# Power.net
KiCad netlist of a schematic drawn in Altium Designer
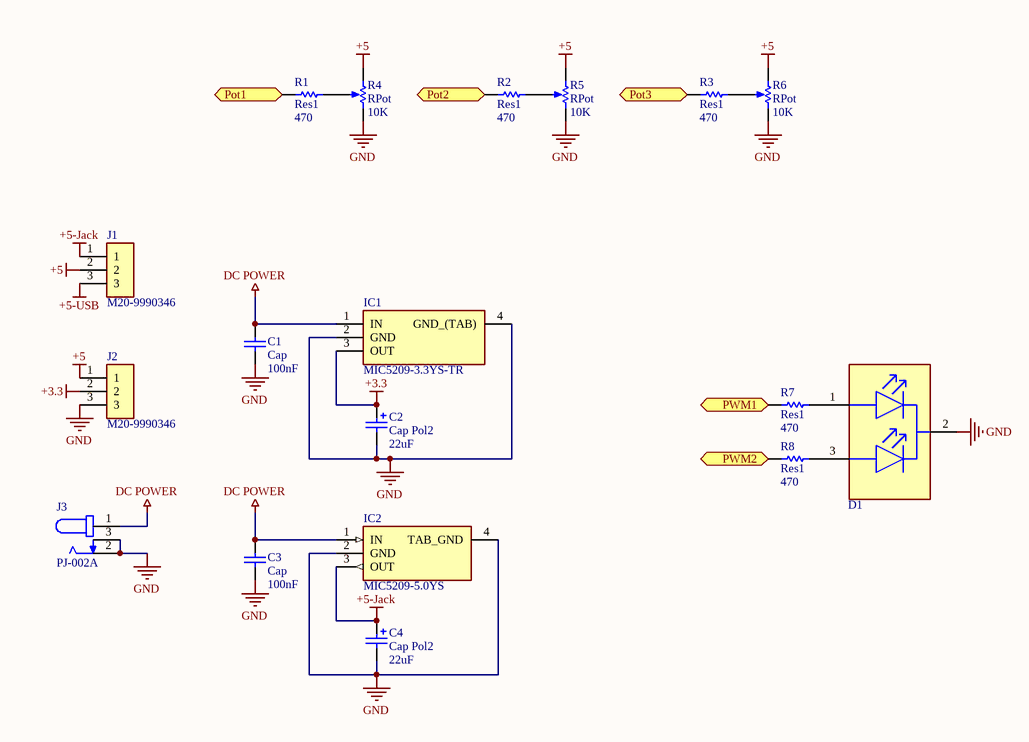
[diagram p0: Power.SchDoc]

(export (version "E")
  (design (tool "Eeschema 10.0.6"))
  (components
    (comp (ref "C1")
      (value "Cap")
      (footprint "Cap 100nF")
      (description "Capacitor")
      (fields (field (name "ALTIUM_VALUE") "100nF") (field (name "PUBLISHER") "Altium Limited"))
      (libsource (lib "APD") (part "Cap"))
    )
    (comp (ref "C2")
      (value "Cap Pol2")
      (footprint "CAP+ 22UF")
      (description "Polarized Capacitor (Axial)")
      (fields (field (name "ALTIUM_VALUE") "22uF") (field (name "PUBLISHER") "Altium Limited"))
      (libsource (lib "APD") (part "Cap Pol2"))
    )
    (comp (ref "C3")
      (value "Cap")
      (footprint "Cap 100nF")
      (description "Capacitor")
      (fields (field (name "ALTIUM_VALUE") "100nF") (field (name "PUBLISHER") "Altium Limited"))
      (libsource (lib "APD") (part "Cap"))
    )
    (comp (ref "C4")
      (value "Cap Pol2")
      (footprint "CAP+ 22UF")
      (description "Polarized Capacitor (Axial)")
      (fields (field (name "ALTIUM_VALUE") "22uF") (field (name "PUBLISHER") "Altium Limited"))
      (libsource (lib "APD") (part "Cap Pol2"))
    )
    (comp (ref "D1")
      (value "LTL1BEKVJNN")
      (footprint "Bicolor LED")
      (libsource (lib "APD") (part "LTL1BEKVJNN"))
    )
    (comp (ref "IC1")
      (value "MIC5209-3.3YS-TR")
      (footprint "LDO")
      (description "Integrated Circuit")
      (fields (field (name "MOUSER PART NUMBER") "998-MIC5209-3.3YSTR"))
      (libsource (lib "APD") (part "MIC5209-3.3YS-TR"))
    )
    (comp (ref "IC2")
      (value "MIC5209-5.0YS")
      (footprint "LDO")
      (description "Integrated Circuit")
      (fields (field (name "MOUSER PART NUMBER") "998-MIC5209-5.0YS"))
      (libsource (lib "APD") (part "MIC5209-5.0YS"))
    )
    (comp (ref "J1")
      (value "M20-9990346")
      (footprint "header 3 pins male")
      (description "Connector")
      (fields (field (name "MOUSER PART NUMBER") "855-M20-9990346"))
      (libsource (lib "APD") (part "M20-9990346"))
    )
    (comp (ref "J2")
      (value "M20-9990346")
      (footprint "Header 3 pins fem.")
      (description "Connector")
      (fields (field (name "MOUSER PART NUMBER") "855-M20-9990346"))
      (libsource (lib "APD") (part "M20-9990346"))
    )
    (comp (ref "J3")
      (value "PJ-002A")
      (footprint "DC Jack")
      (description "DC jack")
      (fields (field (name "MF") "CUI Devices"))
      (libsource (lib "APD") (part "PJ-002A"))
    )
    (comp (ref "R1")
      (value "Res1")
      (footprint "Resistor 1210")
      (description "Resistor")
      (fields (field (name "ALTIUM_VALUE") "470") (field (name "PUBLISHER") "Altium Limited"))
      (libsource (lib "APD") (part "Res1"))
    )
    (comp (ref "R2")
      (value "Res1")
      (footprint "Resistor 1210")
      (description "Resistor")
      (fields (field (name "ALTIUM_VALUE") "470") (field (name "PUBLISHER") "Altium Limited"))
      (libsource (lib "APD") (part "Res1"))
    )
    (comp (ref "R3")
      (value "Res1")
      (footprint "Resistor 1210")
      (description "Resistor")
      (fields (field (name "ALTIUM_VALUE") "470") (field (name "PUBLISHER") "Altium Limited"))
      (libsource (lib "APD") (part "Res1"))
    )
    (comp (ref "R4")
      (value "RPot")
      (footprint "POT")
      (description "Potentiometer")
      (fields (field (name "ALTIUM_VALUE") "10K") (field (name "PUBLISHER") "Altium Limited"))
      (libsource (lib "APD") (part "RPot"))
    )
    (comp (ref "R5")
      (value "RPot")
      (footprint "POT")
      (description "Potentiometer")
      (fields (field (name "ALTIUM_VALUE") "10K") (field (name "PUBLISHER") "Altium Limited"))
      (libsource (lib "APD") (part "RPot"))
    )
    (comp (ref "R6")
      (value "RPot")
      (footprint "POT")
      (description "Potentiometer")
      (fields (field (name "ALTIUM_VALUE") "10K") (field (name "PUBLISHER") "Altium Limited"))
      (libsource (lib "APD") (part "RPot"))
    )
    (comp (ref "R7")
      (value "Res1")
      (footprint "Resistor 1210")
      (description "Resistor")
      (fields (field (name "ALTIUM_VALUE") "470") (field (name "PUBLISHER") "Altium Limited"))
      (libsource (lib "APD") (part "Res1"))
    )
    (comp (ref "R8")
      (value "Res1")
      (footprint "Resistor 1210")
      (description "Resistor")
      (fields (field (name "ALTIUM_VALUE") "470") (field (name "PUBLISHER") "Altium Limited"))
      (libsource (lib "APD") (part "Res1"))
    )
  )
  (nets
    (net (code "1") (name "+3.3") (class "Default")
      (node (ref "C2") (pin "1") (pinfunction "1_1") (pintype "passive"))
      (node (ref "IC1") (pin "3") (pinfunction "OUT_3") (pintype "power_in"))
      (node (ref "J2") (pin "2") (pinfunction "2_2") (pintype "passive"))
    )
    (net (code "2") (name "+5") (class "Default")
      (node (ref "J1") (pin "2") (pinfunction "2_2") (pintype "passive"))
      (node (ref "J2") (pin "1") (pinfunction "1_1") (pintype "passive"))
      (node (ref "R4") (pin "1") (pinfunction "TOP_1") (pintype "passive"))
      (node (ref "R5") (pin "1") (pinfunction "TOP_1") (pintype "passive"))
      (node (ref "R6") (pin "1") (pinfunction "TOP_1") (pintype "passive"))
    )
    (net (code "3") (name "+5-Jack") (class "Default")
      (node (ref "C4") (pin "1") (pinfunction "1_1") (pintype "passive"))
      (node (ref "IC2") (pin "3") (pinfunction "OUT_3") (pintype "output"))
      (node (ref "J1") (pin "1") (pinfunction "1_1") (pintype "passive"))
    )
    (net (code "4") (name "+5-USB") (class "Default")
      (node (ref "J1") (pin "3") (pinfunction "3_3") (pintype "passive"))
    )
    (net (code "5") (name "/PWM1") (class "Default")
      (node (ref "R7") (pin "1") (pinfunction "1_1") (pintype "passive"))
    )
    (net (code "6") (name "/PWM2") (class "Default")
      (node (ref "R8") (pin "1") (pinfunction "1_1") (pintype "passive"))
    )
    (net (code "7") (name "/Pot1") (class "Default")
      (node (ref "R1") (pin "1") (pinfunction "1_1") (pintype "passive"))
    )
    (net (code "8") (name "/Pot2") (class "Default")
      (node (ref "R2") (pin "1") (pinfunction "1_1") (pintype "passive"))
    )
    (net (code "9") (name "/Pot3") (class "Default")
      (node (ref "R3") (pin "1") (pinfunction "1_1") (pintype "passive"))
    )
    (net (code "10") (name "DC POWER") (class "Default")
      (node (ref "C1") (pin "1") (pinfunction "1_1") (pintype "passive"))
      (node (ref "C3") (pin "1") (pinfunction "1_1") (pintype "passive"))
      (node (ref "IC1") (pin "1") (pinfunction "IN_1") (pintype "power_in"))
      (node (ref "IC2") (pin "1") (pinfunction "IN_1") (pintype "input"))
      (node (ref "J3") (pin "1") (pinfunction "1_1") (pintype "passive"))
    )
    (net (code "11") (name "GND") (class "Default")
      (node (ref "C1") (pin "2") (pinfunction "2_2") (pintype "passive"))
      (node (ref "C2") (pin "2") (pinfunction "2_2") (pintype "passive"))
      (node (ref "C3") (pin "2") (pinfunction "2_2") (pintype "passive"))
      (node (ref "C4") (pin "2") (pinfunction "2_2") (pintype "passive"))
      (node (ref "D1") (pin "2") (pinfunction "COMMON_CATHODE_2") (pintype "passive"))
      (node (ref "IC1") (pin "2") (pinfunction "GND_2") (pintype "power_in"))
      (node (ref "IC1") (pin "4") (pinfunction "GND_(TAB)_4") (pintype "passive"))
      (node (ref "IC2") (pin "2") (pinfunction "GND_2") (pintype "power_in"))
      (node (ref "IC2") (pin "4") (pinfunction "TAB_GND_4") (pintype "power_in"))
      (node (ref "J2") (pin "3") (pinfunction "3_3") (pintype "passive"))
      (node (ref "J3") (pin "2") (pinfunction "2_2") (pintype "passive"))
      (node (ref "J3") (pin "3") (pinfunction "3_3") (pintype "passive"))
      (node (ref "R4") (pin "2") (pinfunction "BOT_2") (pintype "passive"))
      (node (ref "R5") (pin "2") (pinfunction "BOT_2") (pintype "passive"))
      (node (ref "R6") (pin "2") (pinfunction "BOT_2") (pintype "passive"))
    )
    (net (code "12") (name "Net-(D1-GREEN_A)") (class "Default")
      (node (ref "D1") (pin "3") (pinfunction "GREEN_A_3") (pintype "passive"))
      (node (ref "R8") (pin "2") (pinfunction "2_2") (pintype "passive"))
    )
    (net (code "13") (name "Net-(D1-RED_A)") (class "Default")
      (node (ref "D1") (pin "1") (pinfunction "RED_A_1") (pintype "passive"))
      (node (ref "R7") (pin "2") (pinfunction "2_2") (pintype "passive"))
    )
    (net (code "14") (name "Net-(R4-TAP)") (class "Default")
      (node (ref "R1") (pin "2") (pinfunction "2_2") (pintype "passive"))
      (node (ref "R4") (pin "3") (pinfunction "TAP_3") (pintype "passive"))
    )
    (net (code "15") (name "Net-(R5-TAP)") (class "Default")
      (node (ref "R2") (pin "2") (pinfunction "2_2") (pintype "passive"))
      (node (ref "R5") (pin "3") (pinfunction "TAP_3") (pintype "passive"))
    )
    (net (code "16") (name "Net-(R6-TAP)") (class "Default")
      (node (ref "R3") (pin "2") (pinfunction "2_2") (pintype "passive"))
      (node (ref "R6") (pin "3") (pinfunction "TAP_3") (pintype "passive"))
    )
  )
)
